# Sheet3.net
KiCad netlist of a schematic drawn in Altium Designer
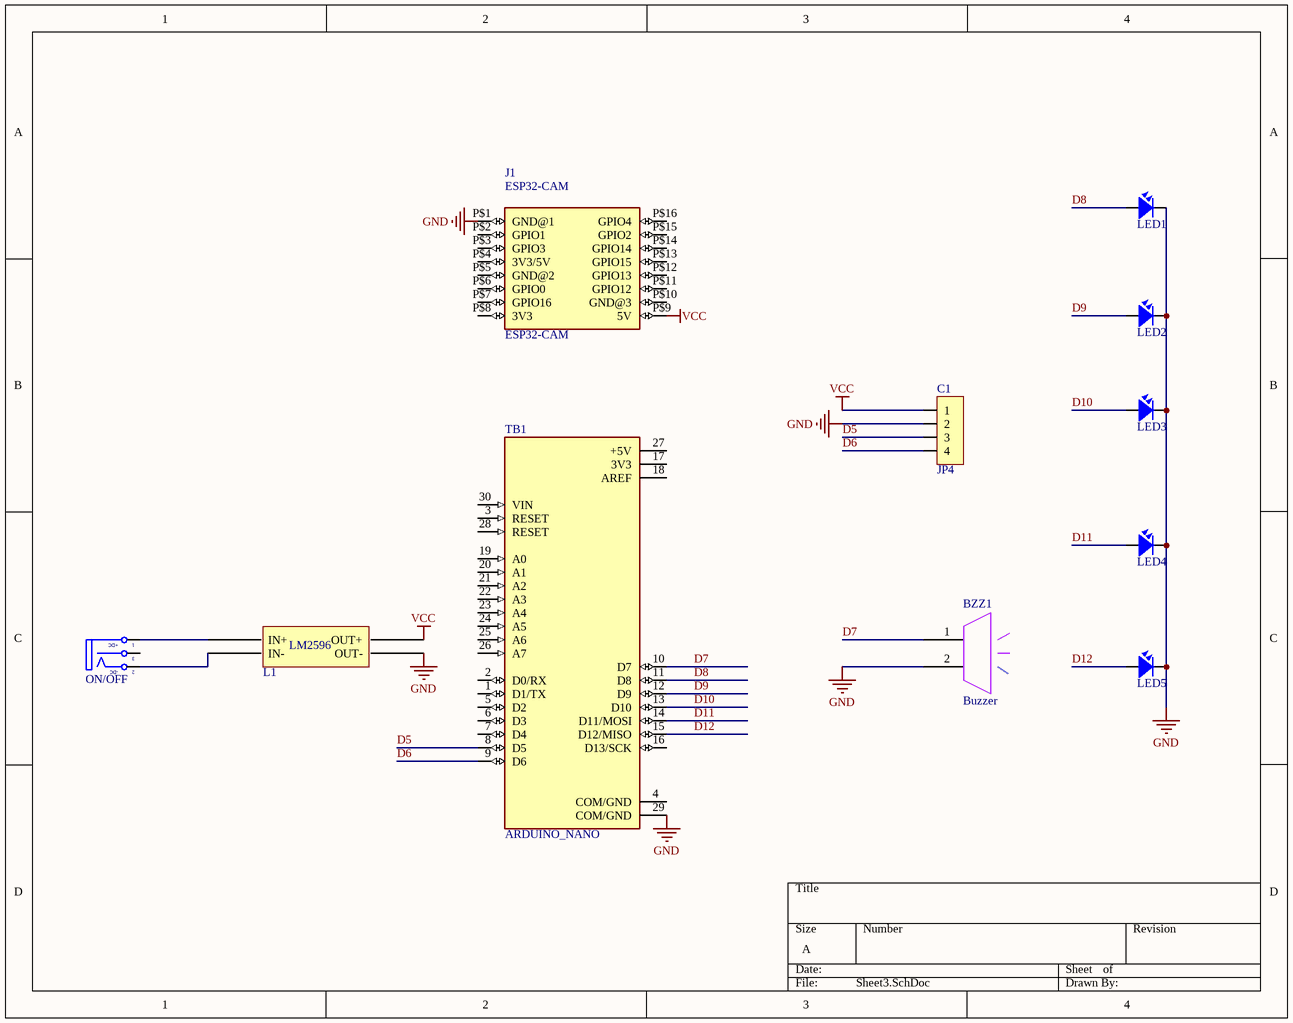
[diagram p0: Sheet3.SchDoc]

(export (version "E")
  (design (tool "Eeschema 10.0.6"))
  (components
    (comp (ref "BZZ1")
      (value "Buzzer")
      (footprint "BUZZER_12.0X8.5MM")
      (libsource (lib "My library altium") (part "Buzzer"))
    )
    (comp (ref "C1")
      (value "JP4")
      (footprint "JP4-C1T")
      (description "WR-PHD 2.54 mm Angled Socket Header")
      (fields
        (field (name "MANUFACTURER") "Würth Elektronik eiSos GmbH")
        (field (name "PARTNO") "613004143121")
        (field (name "CREATED BY") "Karrer Zheng")
      )
      (libsource (lib "LIBRARY") (part "JP4"))
    )
    (comp (ref "J1")
      (value "ESP32-CAM")
      (footprint "ESP32-CAM")
      (fields (field (name "MF") "AI-Thinker"))
      (libsource (lib "ESP32-CAM") (part "ESP32-CAM"))
    )
    (comp (ref "L1")
      (value "BUCK_LM2596")
      (footprint "BUCK_LM2596")
      (libsource (lib "BUCK_LM2596_Library") (part "BUCK_LM2596"))
    )
    (comp (ref "LED1")
      (value "LED")
      (footprint "LED-3MM-YELLOW")
      (description "LED Single colour Green and Red")
      (libsource (lib "LIBRARY") (part "LED"))
    )
    (comp (ref "LED2")
      (value "LED")
      (footprint "LED-3MM-YELLOW")
      (description "LED Single colour Green and Red")
      (libsource (lib "LIBRARY") (part "LED"))
    )
    (comp (ref "LED3")
      (value "LED")
      (footprint "LED-3MM-YELLOW")
      (description "LED Single colour Green and Red")
      (libsource (lib "LIBRARY") (part "LED"))
    )
    (comp (ref "LED4")
      (value "LED")
      (footprint "LED-3MM-YELLOW")
      (description "LED Single colour Green and Red")
      (libsource (lib "LIBRARY") (part "LED"))
    )
    (comp (ref "LED5")
      (value "LED")
      (footprint "LED-3MM-YELLOW")
      (description "LED Single colour Green and Red")
      (libsource (lib "LIBRARY") (part "LED"))
    )
    (comp (ref "ON/OFF")
      (value "POWER")
      (footprint "DC-IN")
      (libsource (lib "My library altium") (part "DCIN"))
    )
    (comp (ref "TB1")
      (value "ARDUINO_NANO")
      (footprint "SHIELD_ARDUINO_NANO")
      (description "Small, complete, and breadboard-friendly board based on the ATmega328 (Arduino Nano 3.x)")
      (fields (field (name "MP") "Arduino Nano") (field (name "MF") "Arduino"))
      (libsource (lib "ARDUINO_NANO") (part "ARDUINO_NANO"))
    )
  )
  (nets
    (net (code "1") (name "/D5") (class "Default")
      (node (ref "C1") (pin "3") (pinfunction "3_3") (pintype "passive"))
      (node (ref "TB1") (pin "8") (pinfunction "D5_8") (pintype "bidirectional"))
    )
    (net (code "2") (name "/D6") (class "Default")
      (node (ref "C1") (pin "4") (pinfunction "4_4") (pintype "passive"))
      (node (ref "TB1") (pin "9") (pinfunction "D6_9") (pintype "bidirectional"))
    )
    (net (code "3") (name "/D7") (class "Default")
      (node (ref "BZZ1") (pin "1") (pinfunction "1_1") (pintype "passive"))
      (node (ref "TB1") (pin "10") (pinfunction "D7_10") (pintype "bidirectional"))
    )
    (net (code "4") (name "/D8") (class "Default")
      (node (ref "LED1") (pin "1") (pinfunction "1_1") (pintype "passive"))
      (node (ref "TB1") (pin "11") (pinfunction "D8_11") (pintype "bidirectional"))
    )
    (net (code "5") (name "/D9") (class "Default")
      (node (ref "LED2") (pin "1") (pinfunction "1_1") (pintype "passive"))
      (node (ref "TB1") (pin "12") (pinfunction "D9_12") (pintype "bidirectional"))
    )
    (net (code "6") (name "/D10") (class "Default")
      (node (ref "LED3") (pin "1") (pinfunction "1_1") (pintype "passive"))
      (node (ref "TB1") (pin "13") (pinfunction "D10_13") (pintype "bidirectional"))
    )
    (net (code "7") (name "/D11") (class "Default")
      (node (ref "LED4") (pin "1") (pinfunction "1_1") (pintype "passive"))
      (node (ref "TB1") (pin "14") (pinfunction "D11/MOSI_14") (pintype "bidirectional"))
    )
    (net (code "8") (name "/D12") (class "Default")
      (node (ref "LED5") (pin "1") (pinfunction "1_1") (pintype "passive"))
      (node (ref "TB1") (pin "15") (pinfunction "D12/MISO_15") (pintype "bidirectional"))
    )
    (net (code "9") (name "GND") (class "Default")
      (node (ref "BZZ1") (pin "2") (pinfunction "2_2") (pintype "passive"))
      (node (ref "C1") (pin "2") (pinfunction "2_2") (pintype "passive"))
      (node (ref "J1") (pin "P$1") (pinfunction "GND@1_P$1") (pintype "bidirectional"))
      (node (ref "L1") (pin "3") (pinfunction "OUT-_3") (pintype "passive"))
      (node (ref "LED1") (pin "2") (pinfunction "2_2") (pintype "passive"))
      (node (ref "LED2") (pin "2") (pinfunction "2_2") (pintype "passive"))
      (node (ref "LED3") (pin "2") (pinfunction "2_2") (pintype "passive"))
      (node (ref "LED4") (pin "2") (pinfunction "2_2") (pintype "passive"))
      (node (ref "LED5") (pin "2") (pinfunction "2_2") (pintype "passive"))
      (node (ref "TB1") (pin "29") (pinfunction "COM/GND_29") (pintype "power_in"))
    )
    (net (code "10") (name "Net-(L1-IN+)") (class "Default")
      (node (ref "L1") (pin "1") (pinfunction "IN+_1") (pintype "passive"))
      (node (ref "ON/OFF") (pin "1") (pinfunction "T_1") (pintype "passive"))
    )
    (net (code "11") (name "Net-(L1-IN-)") (class "Default")
      (node (ref "L1") (pin "2") (pinfunction "IN-_2") (pintype "passive"))
      (node (ref "ON/OFF") (pin "2") (pinfunction "TN_2") (pintype "passive"))
    )
    (net (code "12") (name "VCC") (class "Default")
      (node (ref "C1") (pin "1") (pinfunction "1_1") (pintype "passive"))
      (node (ref "J1") (pin "P$9") (pinfunction "5V_P$9") (pintype "bidirectional"))
      (node (ref "L1") (pin "4") (pinfunction "OUT+_4") (pintype "passive"))
    )
    (net (code "13") (name "unconnected-(J1-3V3-PadP$8)") (class "Default")
      (node (ref "J1") (pin "P$8") (pinfunction "3V3_P$8") (pintype "bidirectional"))
    )
    (net (code "14") (name "unconnected-(J1-3V3{slash}5V-PadP$4)") (class "Default")
      (node (ref "J1") (pin "P$4") (pinfunction "3V3/5V_P$4") (pintype "bidirectional"))
    )
    (net (code "15") (name "unconnected-(J1-GND@2-PadP$5)") (class "Default")
      (node (ref "J1") (pin "P$5") (pinfunction "GND@2_P$5") (pintype "bidirectional"))
    )
    (net (code "16") (name "unconnected-(J1-GND@3-PadP$10)") (class "Default")
      (node (ref "J1") (pin "P$10") (pinfunction "GND@3_P$10") (pintype "bidirectional"))
    )
    (net (code "17") (name "unconnected-(J1-GPIO0-PadP$6)") (class "Default")
      (node (ref "J1") (pin "P$6") (pinfunction "GPIO0_P$6") (pintype "bidirectional"))
    )
    (net (code "18") (name "unconnected-(J1-GPIO1-PadP$2)") (class "Default")
      (node (ref "J1") (pin "P$2") (pinfunction "GPIO1_P$2") (pintype "bidirectional"))
    )
    (net (code "19") (name "unconnected-(J1-GPIO2-PadP$15)") (class "Default")
      (node (ref "J1") (pin "P$15") (pinfunction "GPIO2_P$15") (pintype "bidirectional"))
    )
    (net (code "20") (name "unconnected-(J1-GPIO3-PadP$3)") (class "Default")
      (node (ref "J1") (pin "P$3") (pinfunction "GPIO3_P$3") (pintype "bidirectional"))
    )
    (net (code "21") (name "unconnected-(J1-GPIO4-PadP$16)") (class "Default")
      (node (ref "J1") (pin "P$16") (pinfunction "GPIO4_P$16") (pintype "bidirectional"))
    )
    (net (code "22") (name "unconnected-(J1-GPIO12-PadP$11)") (class "Default")
      (node (ref "J1") (pin "P$11") (pinfunction "GPIO12_P$11") (pintype "bidirectional"))
    )
    (net (code "23") (name "unconnected-(J1-GPIO13-PadP$12)") (class "Default")
      (node (ref "J1") (pin "P$12") (pinfunction "GPIO13_P$12") (pintype "bidirectional"))
    )
    (net (code "24") (name "unconnected-(J1-GPIO14-PadP$14)") (class "Default")
      (node (ref "J1") (pin "P$14") (pinfunction "GPIO14_P$14") (pintype "bidirectional"))
    )
    (net (code "25") (name "unconnected-(J1-GPIO15-PadP$13)") (class "Default")
      (node (ref "J1") (pin "P$13") (pinfunction "GPIO15_P$13") (pintype "bidirectional"))
    )
    (net (code "26") (name "unconnected-(J1-GPIO16-PadP$7)") (class "Default")
      (node (ref "J1") (pin "P$7") (pinfunction "GPIO16_P$7") (pintype "bidirectional"))
    )
    (net (code "27") (name "unconnected-(ON/OFF-S-Pad3)") (class "Default")
      (node (ref "ON/OFF") (pin "3") (pinfunction "S_3") (pintype "power_in"))
    )
    (net (code "28") (name "unconnected-(TB1-+5V-Pad27)") (class "Default")
      (node (ref "TB1") (pin "27") (pinfunction "+5V_27") (pintype "power_in"))
    )
    (net (code "29") (name "unconnected-(TB1-3V3-Pad17)") (class "Default")
      (node (ref "TB1") (pin "17") (pinfunction "3V3_17") (pintype "power_in"))
    )
    (net (code "30") (name "unconnected-(TB1-A0-Pad19)") (class "Default")
      (node (ref "TB1") (pin "19") (pinfunction "A0_19") (pintype "input"))
    )
    (net (code "31") (name "unconnected-(TB1-A1-Pad20)") (class "Default")
      (node (ref "TB1") (pin "20") (pinfunction "A1_20") (pintype "input"))
    )
    (net (code "32") (name "unconnected-(TB1-A2-Pad21)") (class "Default")
      (node (ref "TB1") (pin "21") (pinfunction "A2_21") (pintype "input"))
    )
    (net (code "33") (name "unconnected-(TB1-A3-Pad22)") (class "Default")
      (node (ref "TB1") (pin "22") (pinfunction "A3_22") (pintype "input"))
    )
    (net (code "34") (name "unconnected-(TB1-A4-Pad23)") (class "Default")
      (node (ref "TB1") (pin "23") (pinfunction "A4_23") (pintype "input"))
    )
    (net (code "35") (name "unconnected-(TB1-A5-Pad24)") (class "Default")
      (node (ref "TB1") (pin "24") (pinfunction "A5_24") (pintype "input"))
    )
    (net (code "36") (name "unconnected-(TB1-A6-Pad25)") (class "Default")
      (node (ref "TB1") (pin "25") (pinfunction "A6_25") (pintype "input"))
    )
    (net (code "37") (name "unconnected-(TB1-A7-Pad26)") (class "Default")
      (node (ref "TB1") (pin "26") (pinfunction "A7_26") (pintype "input"))
    )
    (net (code "38") (name "unconnected-(TB1-AREF-Pad18)") (class "Default")
      (node (ref "TB1") (pin "18") (pinfunction "AREF_18") (pintype "power_in"))
    )
    (net (code "39") (name "unconnected-(TB1-COM{slash}GND-Pad4)") (class "Default")
      (node (ref "TB1") (pin "4") (pinfunction "COM/GND_4") (pintype "power_in"))
    )
    (net (code "40") (name "unconnected-(TB1-D0{slash}RX-Pad2)") (class "Default")
      (node (ref "TB1") (pin "2") (pinfunction "D0/RX_2") (pintype "bidirectional"))
    )
    (net (code "41") (name "unconnected-(TB1-D1{slash}TX-Pad1)") (class "Default")
      (node (ref "TB1") (pin "1") (pinfunction "D1/TX_1") (pintype "bidirectional"))
    )
    (net (code "42") (name "unconnected-(TB1-D2-Pad5)") (class "Default")
      (node (ref "TB1") (pin "5") (pinfunction "D2_5") (pintype "bidirectional"))
    )
    (net (code "43") (name "unconnected-(TB1-D3-Pad6)") (class "Default")
      (node (ref "TB1") (pin "6") (pinfunction "D3_6") (pintype "bidirectional"))
    )
    (net (code "44") (name "unconnected-(TB1-D4-Pad7)") (class "Default")
      (node (ref "TB1") (pin "7") (pinfunction "D4_7") (pintype "bidirectional"))
    )
    (net (code "45") (name "unconnected-(TB1-D13{slash}SCK-Pad16)") (class "Default")
      (node (ref "TB1") (pin "16") (pinfunction "D13/SCK_16") (pintype "bidirectional"))
    )
    (net (code "46") (name "unconnected-(TB1-RESET-Pad3)") (class "Default")
      (node (ref "TB1") (pin "3") (pinfunction "RESET_3") (pintype "input"))
    )
    (net (code "47") (name "unconnected-(TB1-RESET-Pad28)") (class "Default")
      (node (ref "TB1") (pin "28") (pinfunction "RESET_28") (pintype "input"))
    )
    (net (code "48") (name "unconnected-(TB1-VIN-Pad30)") (class "Default")
      (node (ref "TB1") (pin "30") (pinfunction "VIN_30") (pintype "input"))
    )
  )
)
